# projekt.net
KiCad netlist of a schematic drawn in EAGLE
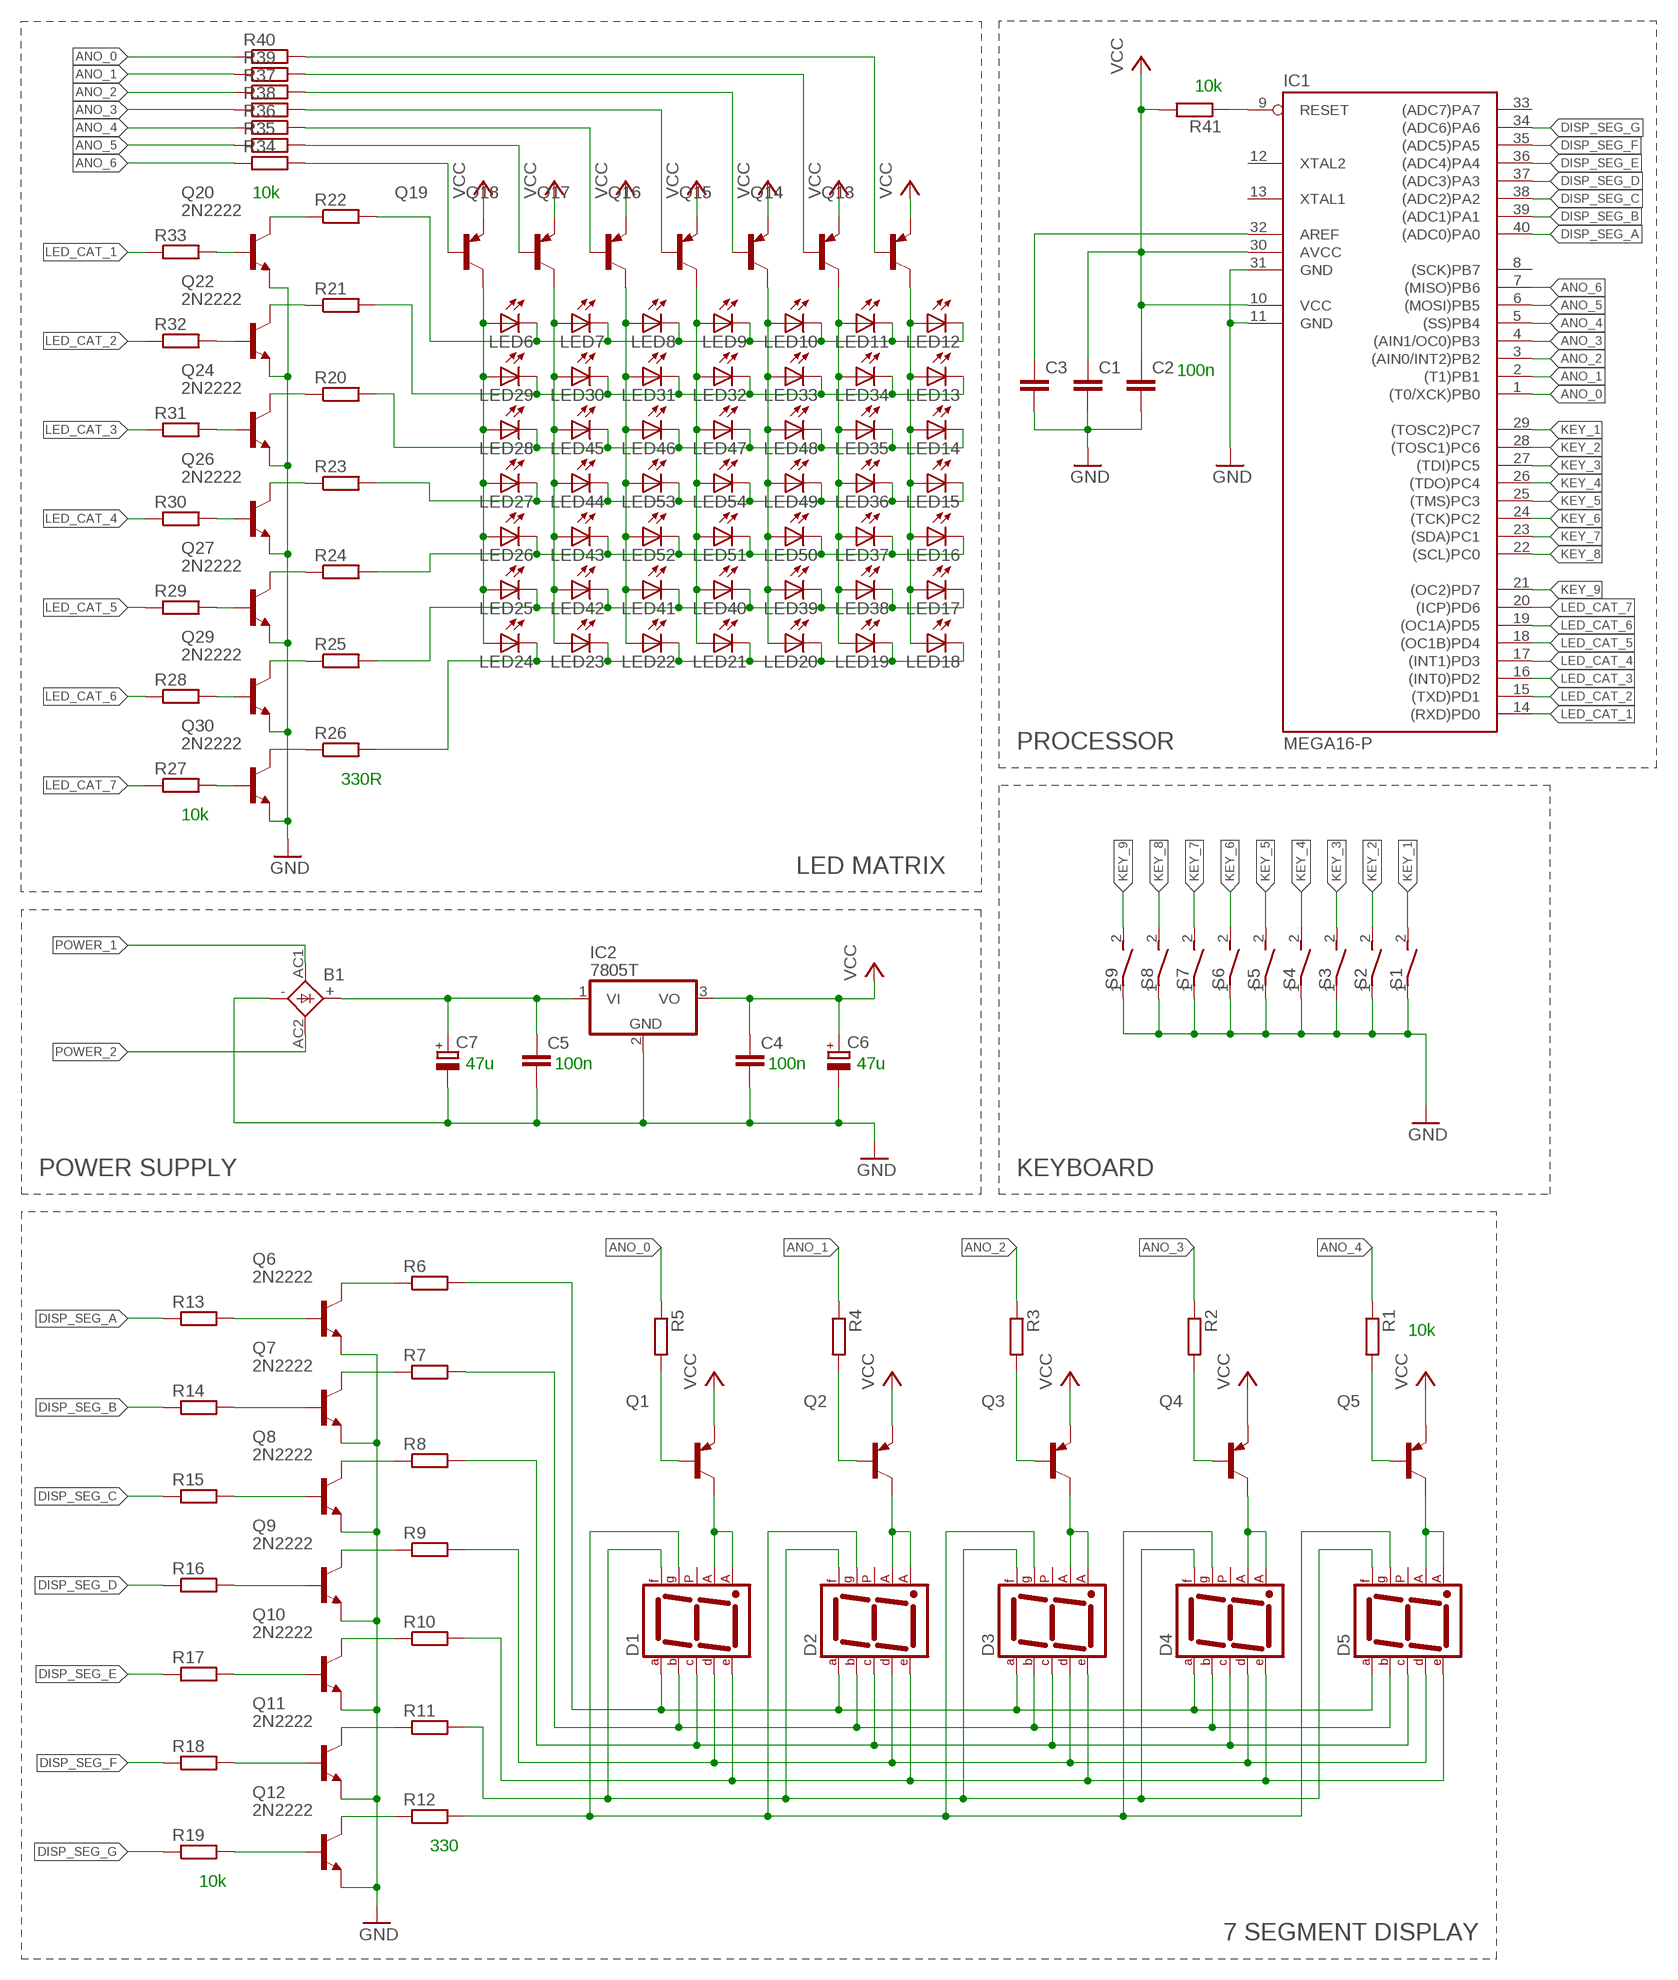
[diagram p0: schematic, sheet 1]

(export (version "E")
  (design (tool "Eeschema 10.0.6"))
  (components
    (comp (ref "B1")
      (value "KBU")
      (footprint "eagle-import:KBU")
      (libsource (lib "eagle-import") (part "KBU"))
    )
    (comp (ref "C1")
      (value "C5/7.2")
      (footprint "eagle-import:C5B7.2")
      (libsource (lib "eagle-import") (part "C5/7.2"))
    )
    (comp (ref "C2")
      (value "C5/7.2")
      (footprint "eagle-import:C5B7.2")
      (libsource (lib "eagle-import") (part "C5/7.2"))
    )
    (comp (ref "C3")
      (value "C5/7.2")
      (footprint "eagle-import:C5B7.2")
      (libsource (lib "eagle-import") (part "C5/7.2"))
    )
    (comp (ref "C4")
      (value "C5/7.2")
      (footprint "eagle-import:C5B7.2")
      (libsource (lib "eagle-import") (part "C5/7.2"))
    )
    (comp (ref "C5")
      (value "C5/7.2")
      (footprint "eagle-import:C5B7.2")
      (libsource (lib "eagle-import") (part "C5/7.2"))
    )
    (comp (ref "C6")
      (value "CPOL-EUB45181C")
      (footprint "eagle-import:B45181C")
      (libsource (lib "eagle-import") (part "CPOL-EUB45181C"))
    )
    (comp (ref "C7")
      (value "CPOL-EUB45181C")
      (footprint "eagle-import:B45181C")
      (libsource (lib "eagle-import") (part "CPOL-EUB45181C"))
    )
    (comp (ref "D1")
      (value "7SEG-CA")
      (footprint "eagle-import:7SEG-13")
      (libsource (lib "eagle-import") (part "7SEG-CA"))
    )
    (comp (ref "D2")
      (value "7SEG-CA")
      (footprint "eagle-import:7SEG-13")
      (libsource (lib "eagle-import") (part "7SEG-CA"))
    )
    (comp (ref "D3")
      (value "7SEG-CA")
      (footprint "eagle-import:7SEG-13")
      (libsource (lib "eagle-import") (part "7SEG-CA"))
    )
    (comp (ref "D4")
      (value "7SEG-CA")
      (footprint "eagle-import:7SEG-13")
      (libsource (lib "eagle-import") (part "7SEG-CA"))
    )
    (comp (ref "D5")
      (value "7SEG-CA")
      (footprint "eagle-import:7SEG-13")
      (libsource (lib "eagle-import") (part "7SEG-CA"))
    )
    (comp (ref "IC1")
      (value "MEGA16-P")
      (footprint "eagle-import:DIL40")
      (fields (field (name "MPN") "ATMEGA16-16PU"))
      (libsource (lib "eagle-import") (part "MEGA16-P"))
    )
    (comp (ref "IC2")
      (value "7805T")
      (footprint "eagle-import:TO220H")
      (libsource (lib "eagle-import") (part "78T05"))
    )
    (comp (ref "LED6")
      (value "LED3MM")
      (footprint "eagle-import:LED3MM")
      (libsource (lib "eagle-import") (part "LED3MM"))
    )
    (comp (ref "LED7")
      (value "LED3MM")
      (footprint "eagle-import:LED3MM")
      (libsource (lib "eagle-import") (part "LED3MM"))
    )
    (comp (ref "LED8")
      (value "LED3MM")
      (footprint "eagle-import:LED3MM")
      (libsource (lib "eagle-import") (part "LED3MM"))
    )
    (comp (ref "LED9")
      (value "LED3MM")
      (footprint "eagle-import:LED3MM")
      (libsource (lib "eagle-import") (part "LED3MM"))
    )
    (comp (ref "LED10")
      (value "LED3MM")
      (footprint "eagle-import:LED3MM")
      (libsource (lib "eagle-import") (part "LED3MM"))
    )
    (comp (ref "LED11")
      (value "LED3MM")
      (footprint "eagle-import:LED3MM")
      (libsource (lib "eagle-import") (part "LED3MM"))
    )
    (comp (ref "LED12")
      (value "LED3MM")
      (footprint "eagle-import:LED3MM")
      (libsource (lib "eagle-import") (part "LED3MM"))
    )
    (comp (ref "LED13")
      (value "LED3MM")
      (footprint "eagle-import:LED3MM")
      (libsource (lib "eagle-import") (part "LED3MM"))
    )
    (comp (ref "LED14")
      (value "LED3MM")
      (footprint "eagle-import:LED3MM")
      (libsource (lib "eagle-import") (part "LED3MM"))
    )
    (comp (ref "LED15")
      (value "LED3MM")
      (footprint "eagle-import:LED3MM")
      (libsource (lib "eagle-import") (part "LED3MM"))
    )
    (comp (ref "LED16")
      (value "LED3MM")
      (footprint "eagle-import:LED3MM")
      (libsource (lib "eagle-import") (part "LED3MM"))
    )
    (comp (ref "LED17")
      (value "LED3MM")
      (footprint "eagle-import:LED3MM")
      (libsource (lib "eagle-import") (part "LED3MM"))
    )
    (comp (ref "LED18")
      (value "LED3MM")
      (footprint "eagle-import:LED3MM")
      (libsource (lib "eagle-import") (part "LED3MM"))
    )
    (comp (ref "LED19")
      (value "LED3MM")
      (footprint "eagle-import:LED3MM")
      (libsource (lib "eagle-import") (part "LED3MM"))
    )
    (comp (ref "LED20")
      (value "LED3MM")
      (footprint "eagle-import:LED3MM")
      (libsource (lib "eagle-import") (part "LED3MM"))
    )
    (comp (ref "LED21")
      (value "LED3MM")
      (footprint "eagle-import:LED3MM")
      (libsource (lib "eagle-import") (part "LED3MM"))
    )
    (comp (ref "LED22")
      (value "LED3MM")
      (footprint "eagle-import:LED3MM")
      (libsource (lib "eagle-import") (part "LED3MM"))
    )
    (comp (ref "LED23")
      (value "LED3MM")
      (footprint "eagle-import:LED3MM")
      (libsource (lib "eagle-import") (part "LED3MM"))
    )
    (comp (ref "LED24")
      (value "LED3MM")
      (footprint "eagle-import:LED3MM")
      (libsource (lib "eagle-import") (part "LED3MM"))
    )
    (comp (ref "LED25")
      (value "LED3MM")
      (footprint "eagle-import:LED3MM")
      (libsource (lib "eagle-import") (part "LED3MM"))
    )
    (comp (ref "LED26")
      (value "LED3MM")
      (footprint "eagle-import:LED3MM")
      (libsource (lib "eagle-import") (part "LED3MM"))
    )
    (comp (ref "LED27")
      (value "LED3MM")
      (footprint "eagle-import:LED3MM")
      (libsource (lib "eagle-import") (part "LED3MM"))
    )
    (comp (ref "LED28")
      (value "LED3MM")
      (footprint "eagle-import:LED3MM")
      (libsource (lib "eagle-import") (part "LED3MM"))
    )
    (comp (ref "LED29")
      (value "LED3MM")
      (footprint "eagle-import:LED3MM")
      (libsource (lib "eagle-import") (part "LED3MM"))
    )
    (comp (ref "LED30")
      (value "LED3MM")
      (footprint "eagle-import:LED3MM")
      (libsource (lib "eagle-import") (part "LED3MM"))
    )
    (comp (ref "LED31")
      (value "LED3MM")
      (footprint "eagle-import:LED3MM")
      (libsource (lib "eagle-import") (part "LED3MM"))
    )
    (comp (ref "LED32")
      (value "LED3MM")
      (footprint "eagle-import:LED3MM")
      (libsource (lib "eagle-import") (part "LED3MM"))
    )
    (comp (ref "LED33")
      (value "LED3MM")
      (footprint "eagle-import:LED3MM")
      (libsource (lib "eagle-import") (part "LED3MM"))
    )
    (comp (ref "LED34")
      (value "LED3MM")
      (footprint "eagle-import:LED3MM")
      (libsource (lib "eagle-import") (part "LED3MM"))
    )
    (comp (ref "LED35")
      (value "LED3MM")
      (footprint "eagle-import:LED3MM")
      (libsource (lib "eagle-import") (part "LED3MM"))
    )
    (comp (ref "LED36")
      (value "LED3MM")
      (footprint "eagle-import:LED3MM")
      (libsource (lib "eagle-import") (part "LED3MM"))
    )
    (comp (ref "LED37")
      (value "LED3MM")
      (footprint "eagle-import:LED3MM")
      (libsource (lib "eagle-import") (part "LED3MM"))
    )
    (comp (ref "LED38")
      (value "LED3MM")
      (footprint "eagle-import:LED3MM")
      (libsource (lib "eagle-import") (part "LED3MM"))
    )
    (comp (ref "LED39")
      (value "LED3MM")
      (footprint "eagle-import:LED3MM")
      (libsource (lib "eagle-import") (part "LED3MM"))
    )
    (comp (ref "LED40")
      (value "LED3MM")
      (footprint "eagle-import:LED3MM")
      (libsource (lib "eagle-import") (part "LED3MM"))
    )
    (comp (ref "LED41")
      (value "LED3MM")
      (footprint "eagle-import:LED3MM")
      (libsource (lib "eagle-import") (part "LED3MM"))
    )
    (comp (ref "LED42")
      (value "LED3MM")
      (footprint "eagle-import:LED3MM")
      (libsource (lib "eagle-import") (part "LED3MM"))
    )
    (comp (ref "LED43")
      (value "LED3MM")
      (footprint "eagle-import:LED3MM")
      (libsource (lib "eagle-import") (part "LED3MM"))
    )
    (comp (ref "LED44")
      (value "LED3MM")
      (footprint "eagle-import:LED3MM")
      (libsource (lib "eagle-import") (part "LED3MM"))
    )
    (comp (ref "LED45")
      (value "LED3MM")
      (footprint "eagle-import:LED3MM")
      (libsource (lib "eagle-import") (part "LED3MM"))
    )
    (comp (ref "LED46")
      (value "LED3MM")
      (footprint "eagle-import:LED3MM")
      (libsource (lib "eagle-import") (part "LED3MM"))
    )
    (comp (ref "LED47")
      (value "LED3MM")
      (footprint "eagle-import:LED3MM")
      (libsource (lib "eagle-import") (part "LED3MM"))
    )
    (comp (ref "LED48")
      (value "LED3MM")
      (footprint "eagle-import:LED3MM")
      (libsource (lib "eagle-import") (part "LED3MM"))
    )
    (comp (ref "LED49")
      (value "LED3MM")
      (footprint "eagle-import:LED3MM")
      (libsource (lib "eagle-import") (part "LED3MM"))
    )
    (comp (ref "LED50")
      (value "LED3MM")
      (footprint "eagle-import:LED3MM")
      (libsource (lib "eagle-import") (part "LED3MM"))
    )
    (comp (ref "LED51")
      (value "LED3MM")
      (footprint "eagle-import:LED3MM")
      (libsource (lib "eagle-import") (part "LED3MM"))
    )
    (comp (ref "LED52")
      (value "LED3MM")
      (footprint "eagle-import:LED3MM")
      (libsource (lib "eagle-import") (part "LED3MM"))
    )
    (comp (ref "LED53")
      (value "LED3MM")
      (footprint "eagle-import:LED3MM")
      (libsource (lib "eagle-import") (part "LED3MM"))
    )
    (comp (ref "LED54")
      (value "LED3MM")
      (footprint "eagle-import:LED3MM")
      (libsource (lib "eagle-import") (part "LED3MM"))
    )
    (comp (ref "Q1")
      (value "-PNP-TO18-")
      (footprint "eagle-import:TO18-")
      (libsource (lib "eagle-import") (part "-PNP-TO18-"))
    )
    (comp (ref "Q2")
      (value "-PNP-TO18-")
      (footprint "eagle-import:TO18-")
      (libsource (lib "eagle-import") (part "-PNP-TO18-"))
    )
    (comp (ref "Q3")
      (value "-PNP-TO18-")
      (footprint "eagle-import:TO18-")
      (libsource (lib "eagle-import") (part "-PNP-TO18-"))
    )
    (comp (ref "Q4")
      (value "-PNP-TO18-")
      (footprint "eagle-import:TO18-")
      (libsource (lib "eagle-import") (part "-PNP-TO18-"))
    )
    (comp (ref "Q5")
      (value "-PNP-TO18-")
      (footprint "eagle-import:TO18-")
      (libsource (lib "eagle-import") (part "-PNP-TO18-"))
    )
    (comp (ref "Q6")
      (value "2N2222")
      (footprint "eagle-import:TO18")
      (libsource (lib "eagle-import") (part "2N2222"))
    )
    (comp (ref "Q7")
      (value "2N2222")
      (footprint "eagle-import:TO18")
      (libsource (lib "eagle-import") (part "2N2222"))
    )
    (comp (ref "Q8")
      (value "2N2222")
      (footprint "eagle-import:TO18")
      (libsource (lib "eagle-import") (part "2N2222"))
    )
    (comp (ref "Q9")
      (value "2N2222")
      (footprint "eagle-import:TO18")
      (libsource (lib "eagle-import") (part "2N2222"))
    )
    (comp (ref "Q10")
      (value "2N2222")
      (footprint "eagle-import:TO18")
      (libsource (lib "eagle-import") (part "2N2222"))
    )
    (comp (ref "Q11")
      (value "2N2222")
      (footprint "eagle-import:TO18")
      (libsource (lib "eagle-import") (part "2N2222"))
    )
    (comp (ref "Q12")
      (value "2N2222")
      (footprint "eagle-import:TO18")
      (libsource (lib "eagle-import") (part "2N2222"))
    )
    (comp (ref "Q13")
      (value "-PNP-TO18-")
      (footprint "eagle-import:TO18-")
      (libsource (lib "eagle-import") (part "-PNP-TO18-"))
    )
    (comp (ref "Q14")
      (value "-PNP-TO18-")
      (footprint "eagle-import:TO18-")
      (libsource (lib "eagle-import") (part "-PNP-TO18-"))
    )
    (comp (ref "Q15")
      (value "-PNP-TO18-")
      (footprint "eagle-import:TO18-")
      (libsource (lib "eagle-import") (part "-PNP-TO18-"))
    )
    (comp (ref "Q16")
      (value "-PNP-TO18-")
      (footprint "eagle-import:TO18-")
      (libsource (lib "eagle-import") (part "-PNP-TO18-"))
    )
    (comp (ref "Q17")
      (value "-PNP-TO18-")
      (footprint "eagle-import:TO18-")
      (libsource (lib "eagle-import") (part "-PNP-TO18-"))
    )
    (comp (ref "Q18")
      (value "-PNP-TO18-")
      (footprint "eagle-import:TO18-")
      (libsource (lib "eagle-import") (part "-PNP-TO18-"))
    )
    (comp (ref "Q19")
      (value "-PNP-TO18-")
      (footprint "eagle-import:TO18-")
      (libsource (lib "eagle-import") (part "-PNP-TO18-"))
    )
    (comp (ref "Q20")
      (value "2N2222")
      (footprint "eagle-import:TO18")
      (libsource (lib "eagle-import") (part "2N2222"))
    )
    (comp (ref "Q22")
      (value "2N2222")
      (footprint "eagle-import:TO18")
      (libsource (lib "eagle-import") (part "2N2222"))
    )
    (comp (ref "Q24")
      (value "2N2222")
      (footprint "eagle-import:TO18")
      (libsource (lib "eagle-import") (part "2N2222"))
    )
    (comp (ref "Q26")
      (value "2N2222")
      (footprint "eagle-import:TO18")
      (libsource (lib "eagle-import") (part "2N2222"))
    )
    (comp (ref "Q27")
      (value "2N2222")
      (footprint "eagle-import:TO18")
      (libsource (lib "eagle-import") (part "2N2222"))
    )
    (comp (ref "Q29")
      (value "2N2222")
      (footprint "eagle-import:TO18")
      (libsource (lib "eagle-import") (part "2N2222"))
    )
    (comp (ref "Q30")
      (value "2N2222")
      (footprint "eagle-import:TO18")
      (libsource (lib "eagle-import") (part "2N2222"))
    )
    (comp (ref "R1")
      (value "R-EU_0204/5")
      (footprint "eagle-import:0204_5")
      (libsource (lib "eagle-import") (part "R-EU_0204/5"))
    )
    (comp (ref "R2")
      (value "R-EU_0204/5")
      (footprint "eagle-import:0204_5")
      (libsource (lib "eagle-import") (part "R-EU_0204/5"))
    )
    (comp (ref "R3")
      (value "R-EU_0204/5")
      (footprint "eagle-import:0204_5")
      (libsource (lib "eagle-import") (part "R-EU_0204/5"))
    )
    (comp (ref "R4")
      (value "R-EU_0204/5")
      (footprint "eagle-import:0204_5")
      (libsource (lib "eagle-import") (part "R-EU_0204/5"))
    )
    (comp (ref "R5")
      (value "R-EU_0204/5")
      (footprint "eagle-import:0204_5")
      (libsource (lib "eagle-import") (part "R-EU_0204/5"))
    )
    (comp (ref "R6")
      (value "R-EU_0204/5")
      (footprint "eagle-import:0204_5")
      (libsource (lib "eagle-import") (part "R-EU_0204/5"))
    )
    (comp (ref "R7")
      (value "R-EU_0204/5")
      (footprint "eagle-import:0204_5")
      (libsource (lib "eagle-import") (part "R-EU_0204/5"))
    )
    (comp (ref "R8")
      (value "R-EU_0204/5")
      (footprint "eagle-import:0204_5")
      (libsource (lib "eagle-import") (part "R-EU_0204/5"))
    )
    (comp (ref "R9")
      (value "R-EU_0204/5")
      (footprint "eagle-import:0204_5")
      (libsource (lib "eagle-import") (part "R-EU_0204/5"))
    )
    (comp (ref "R10")
      (value "R-EU_0204/5")
      (footprint "eagle-import:0204_5")
      (libsource (lib "eagle-import") (part "R-EU_0204/5"))
    )
    (comp (ref "R11")
      (value "R-EU_0204/5")
      (footprint "eagle-import:0204_5")
      (libsource (lib "eagle-import") (part "R-EU_0204/5"))
    )
    (comp (ref "R12")
      (value "R-EU_0204/5")
      (footprint "eagle-import:0204_5")
      (libsource (lib "eagle-import") (part "R-EU_0204/5"))
    )
    (comp (ref "R13")
      (value "R-EU_0204/5")
      (footprint "eagle-import:0204_5")
      (libsource (lib "eagle-import") (part "R-EU_0204/5"))
    )
    (comp (ref "R14")
      (value "R-EU_0204/5")
      (footprint "eagle-import:0204_5")
      (libsource (lib "eagle-import") (part "R-EU_0204/5"))
    )
    (comp (ref "R15")
      (value "R-EU_0204/5")
      (footprint "eagle-import:0204_5")
      (libsource (lib "eagle-import") (part "R-EU_0204/5"))
    )
    (comp (ref "R16")
      (value "R-EU_0204/5")
      (footprint "eagle-import:0204_5")
      (libsource (lib "eagle-import") (part "R-EU_0204/5"))
    )
    (comp (ref "R17")
      (value "R-EU_0204/5")
      (footprint "eagle-import:0204_5")
      (libsource (lib "eagle-import") (part "R-EU_0204/5"))
    )
    (comp (ref "R18")
      (value "R-EU_0204/5")
      (footprint "eagle-import:0204_5")
      (libsource (lib "eagle-import") (part "R-EU_0204/5"))
    )
    (comp (ref "R19")
      (value "R-EU_0204/5")
      (footprint "eagle-import:0204_5")
      (libsource (lib "eagle-import") (part "R-EU_0204/5"))
    )
    (comp (ref "R20")
      (value "R-EU_0204/5")
      (footprint "eagle-import:0204_5")
      (libsource (lib "eagle-import") (part "R-EU_0204/5"))
    )
    (comp (ref "R21")
      (value "R-EU_0204/5")
      (footprint "eagle-import:0204_5")
      (libsource (lib "eagle-import") (part "R-EU_0204/5"))
    )
    (comp (ref "R22")
      (value "R-EU_0204/5")
      (footprint "eagle-import:0204_5")
      (libsource (lib "eagle-import") (part "R-EU_0204/5"))
    )
    (comp (ref "R23")
      (value "R-EU_0204/5")
      (footprint "eagle-import:0204_5")
      (libsource (lib "eagle-import") (part "R-EU_0204/5"))
    )
    (comp (ref "R24")
      (value "R-EU_0204/5")
      (footprint "eagle-import:0204_5")
      (libsource (lib "eagle-import") (part "R-EU_0204/5"))
    )
    (comp (ref "R25")
      (value "R-EU_0204/5")
      (footprint "eagle-import:0204_5")
      (libsource (lib "eagle-import") (part "R-EU_0204/5"))
    )
    (comp (ref "R26")
      (value "R-EU_0204/5")
      (footprint "eagle-import:0204_5")
      (libsource (lib "eagle-import") (part "R-EU_0204/5"))
    )
    (comp (ref "R27")
      (value "R-EU_0204/5")
      (footprint "eagle-import:0204_5")
      (libsource (lib "eagle-import") (part "R-EU_0204/5"))
    )
    (comp (ref "R28")
      (value "R-EU_0204/5")
      (footprint "eagle-import:0204_5")
      (libsource (lib "eagle-import") (part "R-EU_0204/5"))
    )
    (comp (ref "R29")
      (value "R-EU_0204/5")
      (footprint "eagle-import:0204_5")
      (libsource (lib "eagle-import") (part "R-EU_0204/5"))
    )
    (comp (ref "R30")
      (value "R-EU_0204/5")
      (footprint "eagle-import:0204_5")
      (libsource (lib "eagle-import") (part "R-EU_0204/5"))
    )
    (comp (ref "R31")
      (value "R-EU_0204/5")
      (footprint "eagle-import:0204_5")
      (libsource (lib "eagle-import") (part "R-EU_0204/5"))
    )
    (comp (ref "R32")
      (value "R-EU_0204/5")
      (footprint "eagle-import:0204_5")
      (libsource (lib "eagle-import") (part "R-EU_0204/5"))
    )
    (comp (ref "R33")
      (value "R-EU_0204/5")
      (footprint "eagle-import:0204_5")
      (libsource (lib "eagle-import") (part "R-EU_0204/5"))
    )
    (comp (ref "R34")
      (value "R-EU_0204/5")
      (footprint "eagle-import:0204_5")
      (libsource (lib "eagle-import") (part "R-EU_0204/5"))
    )
    (comp (ref "R35")
      (value "R-EU_0204/5")
      (footprint "eagle-import:0204_5")
      (libsource (lib "eagle-import") (part "R-EU_0204/5"))
    )
    (comp (ref "R36")
      (value "R-EU_0204/5")
      (footprint "eagle-import:0204_5")
      (libsource (lib "eagle-import") (part "R-EU_0204/5"))
    )
    (comp (ref "R37")
      (value "R-EU_0204/5")
      (footprint "eagle-import:0204_5")
      (libsource (lib "eagle-import") (part "R-EU_0204/5"))
    )
    (comp (ref "R38")
      (value "R-EU_0204/5")
      (footprint "eagle-import:0204_5")
      (libsource (lib "eagle-import") (part "R-EU_0204/5"))
    )
    (comp (ref "R39")
      (value "R-EU_0204/5")
      (footprint "eagle-import:0204_5")
      (libsource (lib "eagle-import") (part "R-EU_0204/5"))
    )
    (comp (ref "R40")
      (value "R-EU_0204/5")
      (footprint "eagle-import:0204_5")
      (libsource (lib "eagle-import") (part "R-EU_0204/5"))
    )
    (comp (ref "R41")
      (value "R-EU_0204/5")
      (footprint "eagle-import:0204_5")
      (libsource (lib "eagle-import") (part "R-EU_0204/5"))
    )
    (comp (ref "S1")
      (value "DS01E")
      (footprint "eagle-import:DS-01")
      (libsource (lib "eagle-import") (part "DS01E"))
    )
    (comp (ref "S2")
      (value "DS01E")
      (footprint "eagle-import:DS-01")
      (libsource (lib "eagle-import") (part "DS01E"))
    )
    (comp (ref "S3")
      (value "DS01E")
      (footprint "eagle-import:DS-01")
      (libsource (lib "eagle-import") (part "DS01E"))
    )
    (comp (ref "S4")
      (value "DS01E")
      (footprint "eagle-import:DS-01")
      (libsource (lib "eagle-import") (part "DS01E"))
    )
    (comp (ref "S5")
      (value "DS01E")
      (footprint "eagle-import:DS-01")
      (libsource (lib "eagle-import") (part "DS01E"))
    )
    (comp (ref "S6")
      (value "DS01E")
      (footprint "eagle-import:DS-01")
      (libsource (lib "eagle-import") (part "DS01E"))
    )
    (comp (ref "S7")
      (value "DS01E")
      (footprint "eagle-import:DS-01")
      (libsource (lib "eagle-import") (part "DS01E"))
    )
    (comp (ref "S8")
      (value "DS01E")
      (footprint "eagle-import:DS-01")
      (libsource (lib "eagle-import") (part "DS01E"))
    )
    (comp (ref "S9")
      (value "DS01E")
      (footprint "eagle-import:DS-01")
      (libsource (lib "eagle-import") (part "DS01E"))
    )
  )
  (nets
    (net (code "1") (name "ANO_0") (class "Default")
      (node (ref "IC1") (pin "1") (pinfunction "(T0/XCK)PB0_1") (pintype "bidirectional"))
      (node (ref "R40") (pin "1") (pinfunction "1_1") (pintype "passive"))
      (node (ref "R5") (pin "1") (pinfunction "1_1") (pintype "passive"))
    )
    (net (code "2") (name "ANO_1") (class "Default")
      (node (ref "IC1") (pin "2") (pinfunction "(T1)PB1_2") (pintype "bidirectional"))
      (node (ref "R39") (pin "1") (pinfunction "1_1") (pintype "passive"))
      (node (ref "R4") (pin "1") (pinfunction "1_1") (pintype "passive"))
    )
    (net (code "3") (name "ANO_2") (class "Default")
      (node (ref "IC1") (pin "3") (pinfunction "(AIN0/INT2)PB2_3") (pintype "bidirectional"))
      (node (ref "R3") (pin "1") (pinfunction "1_1") (pintype "passive"))
      (node (ref "R37") (pin "1") (pinfunction "1_1") (pintype "passive"))
    )
    (net (code "4") (name "ANO_3") (class "Default")
      (node (ref "IC1") (pin "4") (pinfunction "(AIN1/OC0)PB3_4") (pintype "bidirectional"))
      (node (ref "R2") (pin "1") (pinfunction "1_1") (pintype "passive"))
      (node (ref "R38") (pin "1") (pinfunction "1_1") (pintype "passive"))
    )
    (net (code "5") (name "ANO_4") (class "Default")
      (node (ref "IC1") (pin "5") (pinfunction "(SS)PB4_5") (pintype "bidirectional"))
      (node (ref "R1") (pin "1") (pinfunction "1_1") (pintype "passive"))
      (node (ref "R36") (pin "1") (pinfunction "1_1") (pintype "passive"))
    )
    (net (code "6") (name "ANO_5") (class "Default")
      (node (ref "IC1") (pin "6") (pinfunction "(MOSI)PB5_6") (pintype "bidirectional"))
      (node (ref "R35") (pin "1") (pinfunction "1_1") (pintype "passive"))
    )
    (net (code "7") (name "ANO_6") (class "Default")
      (node (ref "IC1") (pin "7") (pinfunction "(MISO)PB6_7") (pintype "bidirectional"))
      (node (ref "R34") (pin "1") (pinfunction "1_1") (pintype "passive"))
    )
    (net (code "8") (name "DISP_SEG_A") (class "Default")
      (node (ref "IC1") (pin "40") (pinfunction "(ADC0)PA0_40") (pintype "bidirectional"))
      (node (ref "R13") (pin "1") (pinfunction "1_1") (pintype "passive"))
    )
    (net (code "9") (name "DISP_SEG_B") (class "Default")
      (node (ref "IC1") (pin "39") (pinfunction "(ADC1)PA1_39") (pintype "bidirectional"))
      (node (ref "R14") (pin "1") (pinfunction "1_1") (pintype "passive"))
    )
    (net (code "10") (name "DISP_SEG_C") (class "Default")
      (node (ref "IC1") (pin "38") (pinfunction "(ADC2)PA2_38") (pintype "bidirectional"))
      (node (ref "R15") (pin "1") (pinfunction "1_1") (pintype "passive"))
    )
    (net (code "11") (name "DISP_SEG_D") (class "Default")
      (node (ref "IC1") (pin "37") (pinfunction "(ADC3)PA3_37") (pintype "bidirectional"))
      (node (ref "R16") (pin "1") (pinfunction "1_1") (pintype "passive"))
    )
    (net (code "12") (name "DISP_SEG_E") (class "Default")
      (node (ref "IC1") (pin "36") (pinfunction "(ADC4)PA4_36") (pintype "bidirectional"))
      (node (ref "R17") (pin "1") (pinfunction "1_1") (pintype "passive"))
    )
    (net (code "13") (name "DISP_SEG_F") (class "Default")
      (node (ref "IC1") (pin "35") (pinfunction "(ADC5)PA5_35") (pintype "bidirectional"))
      (node (ref "R18") (pin "1") (pinfunction "1_1") (pintype "passive"))
    )
    (net (code "14") (name "DISP_SEG_G") (class "Default")
      (node (ref "IC1") (pin "34") (pinfunction "(ADC6)PA6_34") (pintype "bidirectional"))
      (node (ref "R19") (pin "1") (pinfunction "1_1") (pintype "passive"))
    )
    (net (code "15") (name "GND") (class "Default")
      (node (ref "B1") (pin "-") (pinfunction "-_-") (pintype "passive"))
      (node (ref "C1") (pin "2") (pinfunction "2_2") (pintype "passive"))
      (node (ref "C2") (pin "2") (pinfunction "2_2") (pintype "passive"))
      (node (ref "C3") (pin "2") (pinfunction "2_2") (pintype "passive"))
      (node (ref "C4") (pin "2") (pinfunction "2_2") (pintype "passive"))
      (node (ref "C5") (pin "2") (pinfunction "2_2") (pintype "passive"))
      (node (ref "C6") (pin "-") (pinfunction "-_-") (pintype "passive"))
      (node (ref "C7") (pin "-") (pinfunction "-_-") (pintype "passive"))
      (node (ref "IC1") (pin "11") (pinfunction "GND_11") (pintype "power_in"))
      (node (ref "IC1") (pin "31") (pinfunction "GND_31") (pintype "power_in"))
      (node (ref "IC2") (pin "2") (pinfunction "GND_2") (pintype "passive"))
      (node (ref "Q10") (pin "1") (pinfunction "E_1") (pintype "passive"))
      (node (ref "Q11") (pin "1") (pinfunction "E_1") (pintype "passive"))
      (node (ref "Q12") (pin "1") (pinfunction "E_1") (pintype "passive"))
      (node (ref "Q20") (pin "1") (pinfunction "E_1") (pintype "passive"))
      (node (ref "Q22") (pin "1") (pinfunction "E_1") (pintype "passive"))
      (node (ref "Q24") (pin "1") (pinfunction "E_1") (pintype "passive"))
      (node (ref "Q26") (pin "1") (pinfunction "E_1") (pintype "passive"))
      (node (ref "Q27") (pin "1") (pinfunction "E_1") (pintype "passive"))
      (node (ref "Q29") (pin "1") (pinfunction "E_1") (pintype "passive"))
      (node (ref "Q30") (pin "1") (pinfunction "E_1") (pintype "passive"))
      (node (ref "Q6") (pin "1") (pinfunction "E_1") (pintype "passive"))
      (node (ref "Q7") (pin "1") (pinfunction "E_1") (pintype "passive"))
      (node (ref "Q8") (pin "1") (pinfunction "E_1") (pintype "passive"))
      (node (ref "Q9") (pin "1") (pinfunction "E_1") (pintype "passive"))
      (node (ref "S1") (pin "1") (pinfunction "1_1") (pintype "passive"))
      (node (ref "S2") (pin "1") (pinfunction "1_1") (pintype "passive"))
      (node (ref "S3") (pin "1") (pinfunction "1_1") (pintype "passive"))
      (node (ref "S4") (pin "1") (pinfunction "1_1") (pintype "passive"))
      (node (ref "S5") (pin "1") (pinfunction "1_1") (pintype "passive"))
      (node (ref "S6") (pin "1") (pinfunction "1_1") (pintype "passive"))
      (node (ref "S7") (pin "1") (pinfunction "1_1") (pintype "passive"))
      (node (ref "S8") (pin "1") (pinfunction "1_1") (pintype "passive"))
      (node (ref "S9") (pin "1") (pinfunction "1_1") (pintype "passive"))
    )
    (net (code "16") (name "KEY_1") (class "Default")
      (node (ref "IC1") (pin "29") (pinfunction "(TOSC2)PC7_29") (pintype "bidirectional"))
      (node (ref "S1") (pin "2") (pinfunction "2_2") (pintype "passive"))
    )
    (net (code "17") (name "KEY_2") (class "Default")
      (node (ref "IC1") (pin "28") (pinfunction "(TOSC1)PC6_28") (pintype "bidirectional"))
      (node (ref "S2") (pin "2") (pinfunction "2_2") (pintype "passive"))
    )
    (net (code "18") (name "KEY_3") (class "Default")
      (node (ref "IC1") (pin "27") (pinfunction "(TDI)PC5_27") (pintype "bidirectional"))
      (node (ref "S3") (pin "2") (pinfunction "2_2") (pintype "passive"))
    )
    (net (code "19") (name "KEY_4") (class "Default")
      (node (ref "IC1") (pin "26") (pinfunction "(TDO)PC4_26") (pintype "bidirectional"))
      (node (ref "S4") (pin "2") (pinfunction "2_2") (pintype "passive"))
    )
    (net (code "20") (name "KEY_5") (class "Default")
      (node (ref "IC1") (pin "25") (pinfunction "(TMS)PC3_25") (pintype "bidirectional"))
      (node (ref "S5") (pin "2") (pinfunction "2_2") (pintype "passive"))
    )
    (net (code "21") (name "KEY_6") (class "Default")
      (node (ref "IC1") (pin "24") (pinfunction "(TCK)PC2_24") (pintype "bidirectional"))
      (node (ref "S6") (pin "2") (pinfunction "2_2") (pintype "passive"))
    )
    (net (code "22") (name "KEY_7") (class "Default")
      (node (ref "IC1") (pin "23") (pinfunction "(SDA)PC1_23") (pintype "bidirectional"))
      (node (ref "S7") (pin "2") (pinfunction "2_2") (pintype "passive"))
    )
    (net (code "23") (name "KEY_8") (class "Default")
      (node (ref "IC1") (pin "22") (pinfunction "(SCL)PC0_22") (pintype "bidirectional"))
      (node (ref "S8") (pin "2") (pinfunction "2_2") (pintype "passive"))
    )
    (net (code "24") (name "KEY_9") (class "Default")
      (node (ref "IC1") (pin "21") (pinfunction "(OC2)PD7_21") (pintype "bidirectional"))
      (node (ref "S9") (pin "2") (pinfunction "2_2") (pintype "passive"))
    )
    (net (code "25") (name "LED_CAT_1") (class "Default")
      (node (ref "IC1") (pin "14") (pinfunction "(RXD)PD0_14") (pintype "bidirectional"))
      (node (ref "R33") (pin "1") (pinfunction "1_1") (pintype "passive"))
    )
    (net (code "26") (name "LED_CAT_2") (class "Default")
      (node (ref "IC1") (pin "15") (pinfunction "(TXD)PD1_15") (pintype "bidirectional"))
      (node (ref "R32") (pin "1") (pinfunction "1_1") (pintype "passive"))
    )
    (net (code "27") (name "LED_CAT_3") (class "Default")
      (node (ref "IC1") (pin "16") (pinfunction "(INT0)PD2_16") (pintype "bidirectional"))
      (node (ref "R31") (pin "1") (pinfunction "1_1") (pintype "passive"))
    )
    (net (code "28") (name "LED_CAT_4") (class "Default")
      (node (ref "IC1") (pin "17") (pinfunction "(INT1)PD3_17") (pintype "bidirectional"))
      (node (ref "R30") (pin "1") (pinfunction "1_1") (pintype "passive"))
    )
    (net (code "29") (name "LED_CAT_5") (class "Default")
      (node (ref "IC1") (pin "18") (pinfunction "(OC1B)PD4_18") (pintype "bidirectional"))
      (node (ref "R29") (pin "1") (pinfunction "1_1") (pintype "passive"))
    )
    (net (code "30") (name "LED_CAT_6") (class "Default")
      (node (ref "IC1") (pin "19") (pinfunction "(OC1A)PD5_19") (pintype "bidirectional"))
      (node (ref "R28") (pin "1") (pinfunction "1_1") (pintype "passive"))
    )
    (net (code "31") (name "LED_CAT_7") (class "Default")
      (node (ref "IC1") (pin "20") (pinfunction "(ICP)PD6_20") (pintype "bidirectional"))
      (node (ref "R27") (pin "1") (pinfunction "1_1") (pintype "passive"))
    )
    (net (code "32") (name "Net-(D1-A)") (class "Default")
      (node (ref "D1") (pin "7") (pinfunction "A_7") (pintype "passive"))
      (node (ref "D2") (pin "7") (pinfunction "A_7") (pintype "passive"))
      (node (ref "D3") (pin "7") (pinfunction "A_7") (pintype "passive"))
      (node (ref "D4") (pin "7") (pinfunction "A_7") (pintype "passive"))
      (node (ref "D5") (pin "7") (pinfunction "A_7") (pintype "passive"))
      (node (ref "R6") (pin "2") (pinfunction "2_2") (pintype "passive"))
    )
    (net (code "33") (name "Net-(D1-B)") (class "Default")
      (node (ref "D1") (pin "6") (pinfunction "B_6") (pintype "passive"))
      (node (ref "D2") (pin "6") (pinfunction "B_6") (pintype "passive"))
      (node (ref "D3") (pin "6") (pinfunction "B_6") (pintype "passive"))
      (node (ref "D4") (pin "6") (pinfunction "B_6") (pintype "passive"))
      (node (ref "D5") (pin "6") (pinfunction "B_6") (pintype "passive"))
      (node (ref "R7") (pin "2") (pinfunction "2_2") (pintype "passive"))
    )
    (net (code "34") (name "Net-(D1-C)") (class "Default")
      (node (ref "D1") (pin "4") (pinfunction "C_4") (pintype "passive"))
      (node (ref "D2") (pin "4") (pinfunction "C_4") (pintype "passive"))
      (node (ref "D3") (pin "4") (pinfunction "C_4") (pintype "passive"))
      (node (ref "D4") (pin "4") (pinfunction "C_4") (pintype "passive"))
      (node (ref "D5") (pin "4") (pinfunction "C_4") (pintype "passive"))
      (node (ref "R8") (pin "2") (pinfunction "2_2") (pintype "passive"))
    )
    (net (code "35") (name "Net-(D1-CA1)") (class "Default")
      (node (ref "D1") (pin "3") (pinfunction "CA1_3") (pintype "passive"))
      (node (ref "D1") (pin "8") (pinfunction "CA2_8") (pintype "passive"))
      (node (ref "Q1") (pin "3") (pinfunction "C_3") (pintype "passive"))
    )
    (net (code "36") (name "Net-(D1-D)") (class "Default")
      (node (ref "D1") (pin "2") (pinfunction "D_2") (pintype "passive"))
      (node (ref "D2") (pin "2") (pinfunction "D_2") (pintype "passive"))
      (node (ref "D3") (pin "2") (pinfunction "D_2") (pintype "passive"))
      (node (ref "D4") (pin "2") (pinfunction "D_2") (pintype "passive"))
      (node (ref "D5") (pin "2") (pinfunction "D_2") (pintype "passive"))
      (node (ref "R9") (pin "2") (pinfunction "2_2") (pintype "passive"))
    )
    (net (code "37") (name "Net-(D1-E)") (class "Default")
      (node (ref "D1") (pin "1") (pinfunction "E_1") (pintype "passive"))
      (node (ref "D2") (pin "1") (pinfunction "E_1") (pintype "passive"))
      (node (ref "D3") (pin "1") (pinfunction "E_1") (pintype "passive"))
      (node (ref "D4") (pin "1") (pinfunction "E_1") (pintype "passive"))
      (node (ref "D5") (pin "1") (pinfunction "E_1") (pintype "passive"))
      (node (ref "R10") (pin "2") (pinfunction "2_2") (pintype "passive"))
    )
    (net (code "38") (name "Net-(D1-F)") (class "Default")
      (node (ref "D1") (pin "9") (pinfunction "F_9") (pintype "passive"))
      (node (ref "D2") (pin "9") (pinfunction "F_9") (pintype "passive"))
      (node (ref "D3") (pin "9") (pinfunction "F_9") (pintype "passive"))
      (node (ref "D4") (pin "9") (pinfunction "F_9") (pintype "passive"))
      (node (ref "D5") (pin "9") (pinfunction "F_9") (pintype "passive"))
      (node (ref "R11") (pin "2") (pinfunction "2_2") (pintype "passive"))
    )
    (net (code "39") (name "Net-(D1-G)") (class "Default")
      (node (ref "D1") (pin "10") (pinfunction "G_10") (pintype "passive"))
      (node (ref "D2") (pin "10") (pinfunction "G_10") (pintype "passive"))
      (node (ref "D3") (pin "10") (pinfunction "G_10") (pintype "passive"))
      (node (ref "D4") (pin "10") (pinfunction "G_10") (pintype "passive"))
      (node (ref "D5") (pin "10") (pinfunction "G_10") (pintype "passive"))
      (node (ref "R12") (pin "2") (pinfunction "2_2") (pintype "passive"))
    )
    (net (code "40") (name "Net-(D2-CA1)") (class "Default")
      (node (ref "D2") (pin "3") (pinfunction "CA1_3") (pintype "passive"))
      (node (ref "D2") (pin "8") (pinfunction "CA2_8") (pintype "passive"))
      (node (ref "Q2") (pin "3") (pinfunction "C_3") (pintype "passive"))
    )
    (net (code "41") (name "Net-(D3-CA1)") (class "Default")
      (node (ref "D3") (pin "3") (pinfunction "CA1_3") (pintype "passive"))
      (node (ref "D3") (pin "8") (pinfunction "CA2_8") (pintype "passive"))
      (node (ref "Q3") (pin "3") (pinfunction "C_3") (pintype "passive"))
    )
    (net (code "42") (name "Net-(D4-CA1)") (class "Default")
      (node (ref "D4") (pin "3") (pinfunction "CA1_3") (pintype "passive"))
      (node (ref "D4") (pin "8") (pinfunction "CA2_8") (pintype "passive"))
      (node (ref "Q4") (pin "3") (pinfunction "C_3") (pintype "passive"))
    )
    (net (code "43") (name "Net-(D5-CA1)") (class "Default")
      (node (ref "D5") (pin "3") (pinfunction "CA1_3") (pintype "passive"))
      (node (ref "D5") (pin "8") (pinfunction "CA2_8") (pintype "passive"))
      (node (ref "Q5") (pin "3") (pinfunction "C_3") (pintype "passive"))
    )
    (net (code "44") (name "Net-(IC1-AREF)") (class "Default")
      (node (ref "C3") (pin "1") (pinfunction "1_1") (pintype "passive"))
      (node (ref "IC1") (pin "32") (pinfunction "AREF_32") (pintype "passive"))
    )
    (net (code "45") (name "Net-(IC1-RESET)") (class "Default")
      (node (ref "IC1") (pin "9") (pinfunction "RESET_9") (pintype "input"))
      (node (ref "R41") (pin "1") (pinfunction "1_1") (pintype "passive"))
    )
    (net (code "46") (name "Net-(IC2-VI)") (class "Default")
      (node (ref "B1") (pin "+") (pinfunction "+_+") (pintype "passive"))
      (node (ref "C5") (pin "1") (pinfunction "1_1") (pintype "passive"))
      (node (ref "C7") (pin "+") (pinfunction "+_+") (pintype "passive"))
      (node (ref "IC2") (pin "1") (pinfunction "VI_1") (pintype "input"))
    )
    (net (code "47") (name "Net-(LED10-C)") (class "Default")
      (node (ref "LED10") (pin "K") (pinfunction "C_K") (pintype "passive"))
      (node (ref "LED11") (pin "K") (pinfunction "C_K") (pintype "passive"))
      (node (ref "LED12") (pin "K") (pinfunction "C_K") (pintype "passive"))
      (node (ref "LED6") (pin "K") (pinfunction "C_K") (pintype "passive"))
      (node (ref "LED7") (pin "K") (pinfunction "C_K") (pintype "passive"))
      (node (ref "LED8") (pin "K") (pinfunction "C_K") (pintype "passive"))
      (node (ref "LED9") (pin "K") (pinfunction "C_K") (pintype "passive"))
      (node (ref "R22") (pin "2") (pinfunction "2_2") (pintype "passive"))
    )
    (net (code "48") (name "Net-(LED13-C)") (class "Default")
      (node (ref "LED13") (pin "K") (pinfunction "C_K") (pintype "passive"))
      (node (ref "LED29") (pin "K") (pinfunction "C_K") (pintype "passive"))
      (node (ref "LED30") (pin "K") (pinfunction "C_K") (pintype "passive"))
      (node (ref "LED31") (pin "K") (pinfunction "C_K") (pintype "passive"))
      (node (ref "LED32") (pin "K") (pinfunction "C_K") (pintype "passive"))
      (node (ref "LED33") (pin "K") (pinfunction "C_K") (pintype "passive"))
      (node (ref "LED34") (pin "K") (pinfunction "C_K") (pintype "passive"))
      (node (ref "R21") (pin "2") (pinfunction "2_2") (pintype "passive"))
    )
    (net (code "49") (name "Net-(LED14-C)") (class "Default")
      (node (ref "LED14") (pin "K") (pinfunction "C_K") (pintype "passive"))
      (node (ref "LED28") (pin "K") (pinfunction "C_K") (pintype "passive"))
      (node (ref "LED35") (pin "K") (pinfunction "C_K") (pintype "passive"))
      (node (ref "LED45") (pin "K") (pinfunction "C_K") (pintype "passive"))
      (node (ref "LED46") (pin "K") (pinfunction "C_K") (pintype "passive"))
      (node (ref "LED47") (pin "K") (pinfunction "C_K") (pintype "passive"))
      (node (ref "LED48") (pin "K") (pinfunction "C_K") (pintype "passive"))
      (node (ref "R20") (pin "2") (pinfunction "2_2") (pintype "passive"))
    )
    (net (code "50") (name "Net-(LED15-C)") (class "Default")
      (node (ref "LED15") (pin "K") (pinfunction "C_K") (pintype "passive"))
      (node (ref "LED27") (pin "K") (pinfunction "C_K") (pintype "passive"))
      (node (ref "LED36") (pin "K") (pinfunction "C_K") (pintype "passive"))
      (node (ref "LED44") (pin "K") (pinfunction "C_K") (pintype "passive"))
      (node (ref "LED49") (pin "K") (pinfunction "C_K") (pintype "passive"))
      (node (ref "LED53") (pin "K") (pinfunction "C_K") (pintype "passive"))
      (node (ref "LED54") (pin "K") (pinfunction "C_K") (pintype "passive"))
      (node (ref "R23") (pin "2") (pinfunction "2_2") (pintype "passive"))
    )
    (net (code "51") (name "Net-(LED16-C)") (class "Default")
      (node (ref "LED16") (pin "K") (pinfunction "C_K") (pintype "passive"))
      (node (ref "LED26") (pin "K") (pinfunction "C_K") (pintype "passive"))
      (node (ref "LED37") (pin "K") (pinfunction "C_K") (pintype "passive"))
      (node (ref "LED43") (pin "K") (pinfunction "C_K") (pintype "passive"))
      (node (ref "LED50") (pin "K") (pinfunction "C_K") (pintype "passive"))
      (node (ref "LED51") (pin "K") (pinfunction "C_K") (pintype "passive"))
      (node (ref "LED52") (pin "K") (pinfunction "C_K") (pintype "passive"))
      (node (ref "R24") (pin "2") (pinfunction "2_2") (pintype "passive"))
    )
    (net (code "52") (name "Net-(LED17-C)") (class "Default")
      (node (ref "LED17") (pin "K") (pinfunction "C_K") (pintype "passive"))
      (node (ref "LED25") (pin "K") (pinfunction "C_K") (pintype "passive"))
      (node (ref "LED38") (pin "K") (pinfunction "C_K") (pintype "passive"))
      (node (ref "LED39") (pin "K") (pinfunction "C_K") (pintype "passive"))
      (node (ref "LED40") (pin "K") (pinfunction "C_K") (pintype "passive"))
      (node (ref "LED41") (pin "K") (pinfunction "C_K") (pintype "passive"))
      (node (ref "LED42") (pin "K") (pinfunction "C_K") (pintype "passive"))
      (node (ref "R25") (pin "2") (pinfunction "2_2") (pintype "passive"))
    )
    (net (code "53") (name "Net-(LED18-C)") (class "Default")
      (node (ref "LED18") (pin "K") (pinfunction "C_K") (pintype "passive"))
      (node (ref "LED19") (pin "K") (pinfunction "C_K") (pintype "passive"))
      (node (ref "LED20") (pin "K") (pinfunction "C_K") (pintype "passive"))
      (node (ref "LED21") (pin "K") (pinfunction "C_K") (pintype "passive"))
      (node (ref "LED22") (pin "K") (pinfunction "C_K") (pintype "passive"))
      (node (ref "LED23") (pin "K") (pinfunction "C_K") (pintype "passive"))
      (node (ref "LED24") (pin "K") (pinfunction "C_K") (pintype "passive"))
      (node (ref "R26") (pin "2") (pinfunction "2_2") (pintype "passive"))
    )
    (net (code "54") (name "Net-(Q1-B)") (class "Default")
      (node (ref "Q1") (pin "2") (pinfunction "B_2") (pintype "passive"))
      (node (ref "R5") (pin "2") (pinfunction "2_2") (pintype "passive"))
    )
    (net (code "55") (name "Net-(Q2-B)") (class "Default")
      (node (ref "Q2") (pin "2") (pinfunction "B_2") (pintype "passive"))
      (node (ref "R4") (pin "2") (pinfunction "2_2") (pintype "passive"))
    )
    (net (code "56") (name "Net-(Q3-B)") (class "Default")
      (node (ref "Q3") (pin "2") (pinfunction "B_2") (pintype "passive"))
      (node (ref "R3") (pin "2") (pinfunction "2_2") (pintype "passive"))
    )
    (net (code "57") (name "Net-(Q4-B)") (class "Default")
      (node (ref "Q4") (pin "2") (pinfunction "B_2") (pintype "passive"))
      (node (ref "R2") (pin "2") (pinfunction "2_2") (pintype "passive"))
    )
    (net (code "58") (name "Net-(Q5-B)") (class "Default")
      (node (ref "Q5") (pin "2") (pinfunction "B_2") (pintype "passive"))
      (node (ref "R1") (pin "2") (pinfunction "2_2") (pintype "passive"))
    )
    (net (code "59") (name "Net-(Q6-B)") (class "Default")
      (node (ref "Q6") (pin "2") (pinfunction "B_2") (pintype "passive"))
      (node (ref "R13") (pin "2") (pinfunction "2_2") (pintype "passive"))
    )
    (net (code "60") (name "Net-(Q6-C)") (class "Default")
      (node (ref "Q6") (pin "3") (pinfunction "C_3") (pintype "passive"))
      (node (ref "R6") (pin "1") (pinfunction "1_1") (pintype "passive"))
    )
    (net (code "61") (name "Net-(Q7-B)") (class "Default")
      (node (ref "Q7") (pin "2") (pinfunction "B_2") (pintype "passive"))
      (node (ref "R14") (pin "2") (pinfunction "2_2") (pintype "passive"))
    )
    (net (code "62") (name "Net-(Q7-C)") (class "Default")
      (node (ref "Q7") (pin "3") (pinfunction "C_3") (pintype "passive"))
      (node (ref "R7") (pin "1") (pinfunction "1_1") (pintype "passive"))
    )
    (net (code "63") (name "Net-(Q8-B)") (class "Default")
      (node (ref "Q8") (pin "2") (pinfunction "B_2") (pintype "passive"))
      (node (ref "R15") (pin "2") (pinfunction "2_2") (pintype "passive"))
    )
    (net (code "64") (name "Net-(Q8-C)") (class "Default")
      (node (ref "Q8") (pin "3") (pinfunction "C_3") (pintype "passive"))
      (node (ref "R8") (pin "1") (pinfunction "1_1") (pintype "passive"))
    )
    (net (code "65") (name "Net-(Q9-B)") (class "Default")
      (node (ref "Q9") (pin "2") (pinfunction "B_2") (pintype "passive"))
      (node (ref "R16") (pin "2") (pinfunction "2_2") (pintype "passive"))
    )
    (net (code "66") (name "Net-(Q9-C)") (class "Default")
      (node (ref "Q9") (pin "3") (pinfunction "C_3") (pintype "passive"))
      (node (ref "R9") (pin "1") (pinfunction "1_1") (pintype "passive"))
    )
    (net (code "67") (name "Net-(Q10-B)") (class "Default")
      (node (ref "Q10") (pin "2") (pinfunction "B_2") (pintype "passive"))
      (node (ref "R17") (pin "2") (pinfunction "2_2") (pintype "passive"))
    )
    (net (code "68") (name "Net-(Q10-C)") (class "Default")
      (node (ref "Q10") (pin "3") (pinfunction "C_3") (pintype "passive"))
      (node (ref "R10") (pin "1") (pinfunction "1_1") (pintype "passive"))
    )
    (net (code "69") (name "Net-(Q11-B)") (class "Default")
      (node (ref "Q11") (pin "2") (pinfunction "B_2") (pintype "passive"))
      (node (ref "R18") (pin "2") (pinfunction "2_2") (pintype "passive"))
    )
    (net (code "70") (name "Net-(Q11-C)") (class "Default")
      (node (ref "Q11") (pin "3") (pinfunction "C_3") (pintype "passive"))
      (node (ref "R11") (pin "1") (pinfunction "1_1") (pintype "passive"))
    )
    (net (code "71") (name "Net-(Q12-B)") (class "Default")
      (node (ref "Q12") (pin "2") (pinfunction "B_2") (pintype "passive"))
      (node (ref "R19") (pin "2") (pinfunction "2_2") (pintype "passive"))
    )
    (net (code "72") (name "Net-(Q12-C)") (class "Default")
      (node (ref "Q12") (pin "3") (pinfunction "C_3") (pintype "passive"))
      (node (ref "R12") (pin "1") (pinfunction "1_1") (pintype "passive"))
    )
    (net (code "73") (name "Net-(Q13-B)") (class "Default")
      (node (ref "Q13") (pin "2") (pinfunction "B_2") (pintype "passive"))
      (node (ref "R40") (pin "2") (pinfunction "2_2") (pintype "passive"))
    )
    (net (code "74") (name "Net-(Q13-C)") (class "Default")
      (node (ref "LED12") (pin "A") (pinfunction "A_A") (pintype "passive"))
      (node (ref "LED13") (pin "A") (pinfunction "A_A") (pintype "passive"))
      (node (ref "LED14") (pin "A") (pinfunction "A_A") (pintype "passive"))
      (node (ref "LED15") (pin "A") (pinfunction "A_A") (pintype "passive"))
      (node (ref "LED16") (pin "A") (pinfunction "A_A") (pintype "passive"))
      (node (ref "LED17") (pin "A") (pinfunction "A_A") (pintype "passive"))
      (node (ref "LED18") (pin "A") (pinfunction "A_A") (pintype "passive"))
      (node (ref "Q13") (pin "3") (pinfunction "C_3") (pintype "passive"))
    )
    (net (code "75") (name "Net-(Q14-B)") (class "Default")
      (node (ref "Q14") (pin "2") (pinfunction "B_2") (pintype "passive"))
      (node (ref "R39") (pin "2") (pinfunction "2_2") (pintype "passive"))
    )
    (net (code "76") (name "Net-(Q14-C)") (class "Default")
      (node (ref "LED11") (pin "A") (pinfunction "A_A") (pintype "passive"))
      (node (ref "LED19") (pin "A") (pinfunction "A_A") (pintype "passive"))
      (node (ref "LED34") (pin "A") (pinfunction "A_A") (pintype "passive"))
      (node (ref "LED35") (pin "A") (pinfunction "A_A") (pintype "passive"))
      (node (ref "LED36") (pin "A") (pinfunction "A_A") (pintype "passive"))
      (node (ref "LED37") (pin "A") (pinfunction "A_A") (pintype "passive"))
      (node (ref "LED38") (pin "A") (pinfunction "A_A") (pintype "passive"))
      (node (ref "Q14") (pin "3") (pinfunction "C_3") (pintype "passive"))
    )
    (net (code "77") (name "Net-(Q15-B)") (class "Default")
      (node (ref "Q15") (pin "2") (pinfunction "B_2") (pintype "passive"))
      (node (ref "R37") (pin "2") (pinfunction "2_2") (pintype "passive"))
    )
    (net (code "78") (name "Net-(Q15-C)") (class "Default")
      (node (ref "LED10") (pin "A") (pinfunction "A_A") (pintype "passive"))
      (node (ref "LED20") (pin "A") (pinfunction "A_A") (pintype "passive"))
      (node (ref "LED33") (pin "A") (pinfunction "A_A") (pintype "passive"))
      (node (ref "LED39") (pin "A") (pinfunction "A_A") (pintype "passive"))
      (node (ref "LED48") (pin "A") (pinfunction "A_A") (pintype "passive"))
      (node (ref "LED49") (pin "A") (pinfunction "A_A") (pintype "passive"))
      (node (ref "LED50") (pin "A") (pinfunction "A_A") (pintype "passive"))
      (node (ref "Q15") (pin "3") (pinfunction "C_3") (pintype "passive"))
    )
    (net (code "79") (name "Net-(Q16-B)") (class "Default")
      (node (ref "Q16") (pin "2") (pinfunction "B_2") (pintype "passive"))
      (node (ref "R38") (pin "2") (pinfunction "2_2") (pintype "passive"))
    )
    (net (code "80") (name "Net-(Q16-C)") (class "Default")
      (node (ref "LED21") (pin "A") (pinfunction "A_A") (pintype "passive"))
      (node (ref "LED32") (pin "A") (pinfunction "A_A") (pintype "passive"))
      (node (ref "LED40") (pin "A") (pinfunction "A_A") (pintype "passive"))
      (node (ref "LED47") (pin "A") (pinfunction "A_A") (pintype "passive"))
      (node (ref "LED51") (pin "A") (pinfunction "A_A") (pintype "passive"))
      (node (ref "LED54") (pin "A") (pinfunction "A_A") (pintype "passive"))
      (node (ref "LED9") (pin "A") (pinfunction "A_A") (pintype "passive"))
      (node (ref "Q16") (pin "3") (pinfunction "C_3") (pintype "passive"))
    )
    (net (code "81") (name "Net-(Q17-B)") (class "Default")
      (node (ref "Q17") (pin "2") (pinfunction "B_2") (pintype "passive"))
      (node (ref "R36") (pin "2") (pinfunction "2_2") (pintype "passive"))
    )
    (net (code "82") (name "Net-(Q17-C)") (class "Default")
      (node (ref "LED22") (pin "A") (pinfunction "A_A") (pintype "passive"))
      (node (ref "LED31") (pin "A") (pinfunction "A_A") (pintype "passive"))
      (node (ref "LED41") (pin "A") (pinfunction "A_A") (pintype "passive"))
      (node (ref "LED46") (pin "A") (pinfunction "A_A") (pintype "passive"))
      (node (ref "LED52") (pin "A") (pinfunction "A_A") (pintype "passive"))
      (node (ref "LED53") (pin "A") (pinfunction "A_A") (pintype "passive"))
      (node (ref "LED8") (pin "A") (pinfunction "A_A") (pintype "passive"))
      (node (ref "Q17") (pin "3") (pinfunction "C_3") (pintype "passive"))
    )
    (net (code "83") (name "Net-(Q18-B)") (class "Default")
      (node (ref "Q18") (pin "2") (pinfunction "B_2") (pintype "passive"))
      (node (ref "R35") (pin "2") (pinfunction "2_2") (pintype "passive"))
    )
    (net (code "84") (name "Net-(Q18-C)") (class "Default")
      (node (ref "LED23") (pin "A") (pinfunction "A_A") (pintype "passive"))
      (node (ref "LED30") (pin "A") (pinfunction "A_A") (pintype "passive"))
      (node (ref "LED42") (pin "A") (pinfunction "A_A") (pintype "passive"))
      (node (ref "LED43") (pin "A") (pinfunction "A_A") (pintype "passive"))
      (node (ref "LED44") (pin "A") (pinfunction "A_A") (pintype "passive"))
      (node (ref "LED45") (pin "A") (pinfunction "A_A") (pintype "passive"))
      (node (ref "LED7") (pin "A") (pinfunction "A_A") (pintype "passive"))
      (node (ref "Q18") (pin "3") (pinfunction "C_3") (pintype "passive"))
    )
    (net (code "85") (name "Net-(Q19-B)") (class "Default")
      (node (ref "Q19") (pin "2") (pinfunction "B_2") (pintype "passive"))
      (node (ref "R34") (pin "2") (pinfunction "2_2") (pintype "passive"))
    )
    (net (code "86") (name "Net-(Q19-C)") (class "Default")
      (node (ref "LED24") (pin "A") (pinfunction "A_A") (pintype "passive"))
      (node (ref "LED25") (pin "A") (pinfunction "A_A") (pintype "passive"))
      (node (ref "LED26") (pin "A") (pinfunction "A_A") (pintype "passive"))
      (node (ref "LED27") (pin "A") (pinfunction "A_A") (pintype "passive"))
      (node (ref "LED28") (pin "A") (pinfunction "A_A") (pintype "passive"))
      (node (ref "LED29") (pin "A") (pinfunction "A_A") (pintype "passive"))
      (node (ref "LED6") (pin "A") (pinfunction "A_A") (pintype "passive"))
      (node (ref "Q19") (pin "3") (pinfunction "C_3") (pintype "passive"))
    )
    (net (code "87") (name "Net-(Q20-B)") (class "Default")
      (node (ref "Q20") (pin "2") (pinfunction "B_2") (pintype "passive"))
      (node (ref "R33") (pin "2") (pinfunction "2_2") (pintype "passive"))
    )
    (net (code "88") (name "Net-(Q20-C)") (class "Default")
      (node (ref "Q20") (pin "3") (pinfunction "C_3") (pintype "passive"))
      (node (ref "R22") (pin "1") (pinfunction "1_1") (pintype "passive"))
    )
    (net (code "89") (name "Net-(Q22-B)") (class "Default")
      (node (ref "Q22") (pin "2") (pinfunction "B_2") (pintype "passive"))
      (node (ref "R32") (pin "2") (pinfunction "2_2") (pintype "passive"))
    )
    (net (code "90") (name "Net-(Q22-C)") (class "Default")
      (node (ref "Q22") (pin "3") (pinfunction "C_3") (pintype "passive"))
      (node (ref "R21") (pin "1") (pinfunction "1_1") (pintype "passive"))
    )
    (net (code "91") (name "Net-(Q24-B)") (class "Default")
      (node (ref "Q24") (pin "2") (pinfunction "B_2") (pintype "passive"))
      (node (ref "R31") (pin "2") (pinfunction "2_2") (pintype "passive"))
    )
    (net (code "92") (name "Net-(Q24-C)") (class "Default")
      (node (ref "Q24") (pin "3") (pinfunction "C_3") (pintype "passive"))
      (node (ref "R20") (pin "1") (pinfunction "1_1") (pintype "passive"))
    )
    (net (code "93") (name "Net-(Q26-B)") (class "Default")
      (node (ref "Q26") (pin "2") (pinfunction "B_2") (pintype "passive"))
      (node (ref "R30") (pin "2") (pinfunction "2_2") (pintype "passive"))
    )
    (net (code "94") (name "Net-(Q26-C)") (class "Default")
      (node (ref "Q26") (pin "3") (pinfunction "C_3") (pintype "passive"))
      (node (ref "R23") (pin "1") (pinfunction "1_1") (pintype "passive"))
    )
    (net (code "95") (name "Net-(Q27-B)") (class "Default")
      (node (ref "Q27") (pin "2") (pinfunction "B_2") (pintype "passive"))
      (node (ref "R29") (pin "2") (pinfunction "2_2") (pintype "passive"))
    )
    (net (code "96") (name "Net-(Q27-C)") (class "Default")
      (node (ref "Q27") (pin "3") (pinfunction "C_3") (pintype "passive"))
      (node (ref "R24") (pin "1") (pinfunction "1_1") (pintype "passive"))
    )
    (net (code "97") (name "Net-(Q29-B)") (class "Default")
      (node (ref "Q29") (pin "2") (pinfunction "B_2") (pintype "passive"))
      (node (ref "R28") (pin "2") (pinfunction "2_2") (pintype "passive"))
    )
    (net (code "98") (name "Net-(Q29-C)") (class "Default")
      (node (ref "Q29") (pin "3") (pinfunction "C_3") (pintype "passive"))
      (node (ref "R25") (pin "1") (pinfunction "1_1") (pintype "passive"))
    )
    (net (code "99") (name "Net-(Q30-B)") (class "Default")
      (node (ref "Q30") (pin "2") (pinfunction "B_2") (pintype "passive"))
      (node (ref "R27") (pin "2") (pinfunction "2_2") (pintype "passive"))
    )
    (net (code "100") (name "Net-(Q30-C)") (class "Default")
      (node (ref "Q30") (pin "3") (pinfunction "C_3") (pintype "passive"))
      (node (ref "R26") (pin "1") (pinfunction "1_1") (pintype "passive"))
    )
    (net (code "101") (name "POWER_1") (class "Default")
      (node (ref "B1") (pin "AC1") (pinfunction "AC1_AC1") (pintype "passive"))
    )
    (net (code "102") (name "POWER_2") (class "Default")
      (node (ref "B1") (pin "AC2") (pinfunction "AC2_AC2") (pintype "passive"))
    )
    (net (code "103") (name "VCC") (class "Default")
      (node (ref "C1") (pin "1") (pinfunction "1_1") (pintype "passive"))
      (node (ref "C2") (pin "1") (pinfunction "1_1") (pintype "passive"))
      (node (ref "C4") (pin "1") (pinfunction "1_1") (pintype "passive"))
      (node (ref "C6") (pin "+") (pinfunction "+_+") (pintype "passive"))
      (node (ref "IC1") (pin "10") (pinfunction "VCC_10") (pintype "power_in"))
      (node (ref "IC1") (pin "30") (pinfunction "AVCC_30") (pintype "power_in"))
      (node (ref "IC2") (pin "3") (pinfunction "VO_3") (pintype "passive"))
      (node (ref "Q1") (pin "1") (pinfunction "E_1") (pintype "passive"))
      (node (ref "Q13") (pin "1") (pinfunction "E_1") (pintype "passive"))
      (node (ref "Q14") (pin "1") (pinfunction "E_1") (pintype "passive"))
      (node (ref "Q15") (pin "1") (pinfunction "E_1") (pintype "passive"))
      (node (ref "Q16") (pin "1") (pinfunction "E_1") (pintype "passive"))
      (node (ref "Q17") (pin "1") (pinfunction "E_1") (pintype "passive"))
      (node (ref "Q18") (pin "1") (pinfunction "E_1") (pintype "passive"))
      (node (ref "Q19") (pin "1") (pinfunction "E_1") (pintype "passive"))
      (node (ref "Q2") (pin "1") (pinfunction "E_1") (pintype "passive"))
      (node (ref "Q3") (pin "1") (pinfunction "E_1") (pintype "passive"))
      (node (ref "Q4") (pin "1") (pinfunction "E_1") (pintype "passive"))
      (node (ref "Q5") (pin "1") (pinfunction "E_1") (pintype "passive"))
      (node (ref "R41") (pin "2") (pinfunction "2_2") (pintype "passive"))
    )
    (net (code "104") (name "unconnected-(D1-DP-Pad5)") (class "Default")
      (node (ref "D1") (pin "5") (pinfunction "DP_5") (pintype "passive"))
    )
    (net (code "105") (name "unconnected-(D2-DP-Pad5)") (class "Default")
      (node (ref "D2") (pin "5") (pinfunction "DP_5") (pintype "passive"))
    )
    (net (code "106") (name "unconnected-(D3-DP-Pad5)") (class "Default")
      (node (ref "D3") (pin "5") (pinfunction "DP_5") (pintype "passive"))
    )
    (net (code "107") (name "unconnected-(D4-DP-Pad5)") (class "Default")
      (node (ref "D4") (pin "5") (pinfunction "DP_5") (pintype "passive"))
    )
    (net (code "108") (name "unconnected-(D5-DP-Pad5)") (class "Default")
      (node (ref "D5") (pin "5") (pinfunction "DP_5") (pintype "passive"))
    )
    (net (code "109") (name "unconnected-(IC1-(ADC7)PA7-Pad33)") (class "Default")
      (node (ref "IC1") (pin "33") (pinfunction "(ADC7)PA7_33") (pintype "bidirectional"))
    )
    (net (code "110") (name "unconnected-(IC1-(SCK)PB7-Pad8)") (class "Default")
      (node (ref "IC1") (pin "8") (pinfunction "(SCK)PB7_8") (pintype "bidirectional"))
    )
    (net (code "111") (name "unconnected-(IC1-XTAL1-Pad13)") (class "Default")
      (node (ref "IC1") (pin "13") (pinfunction "XTAL1_13") (pintype "bidirectional"))
    )
    (net (code "112") (name "unconnected-(IC1-XTAL2-Pad12)") (class "Default")
      (node (ref "IC1") (pin "12") (pinfunction "XTAL2_12") (pintype "bidirectional"))
    )
  )
)
